# imu_junction.net
KiCad netlist of a schematic drawn in EAGLE
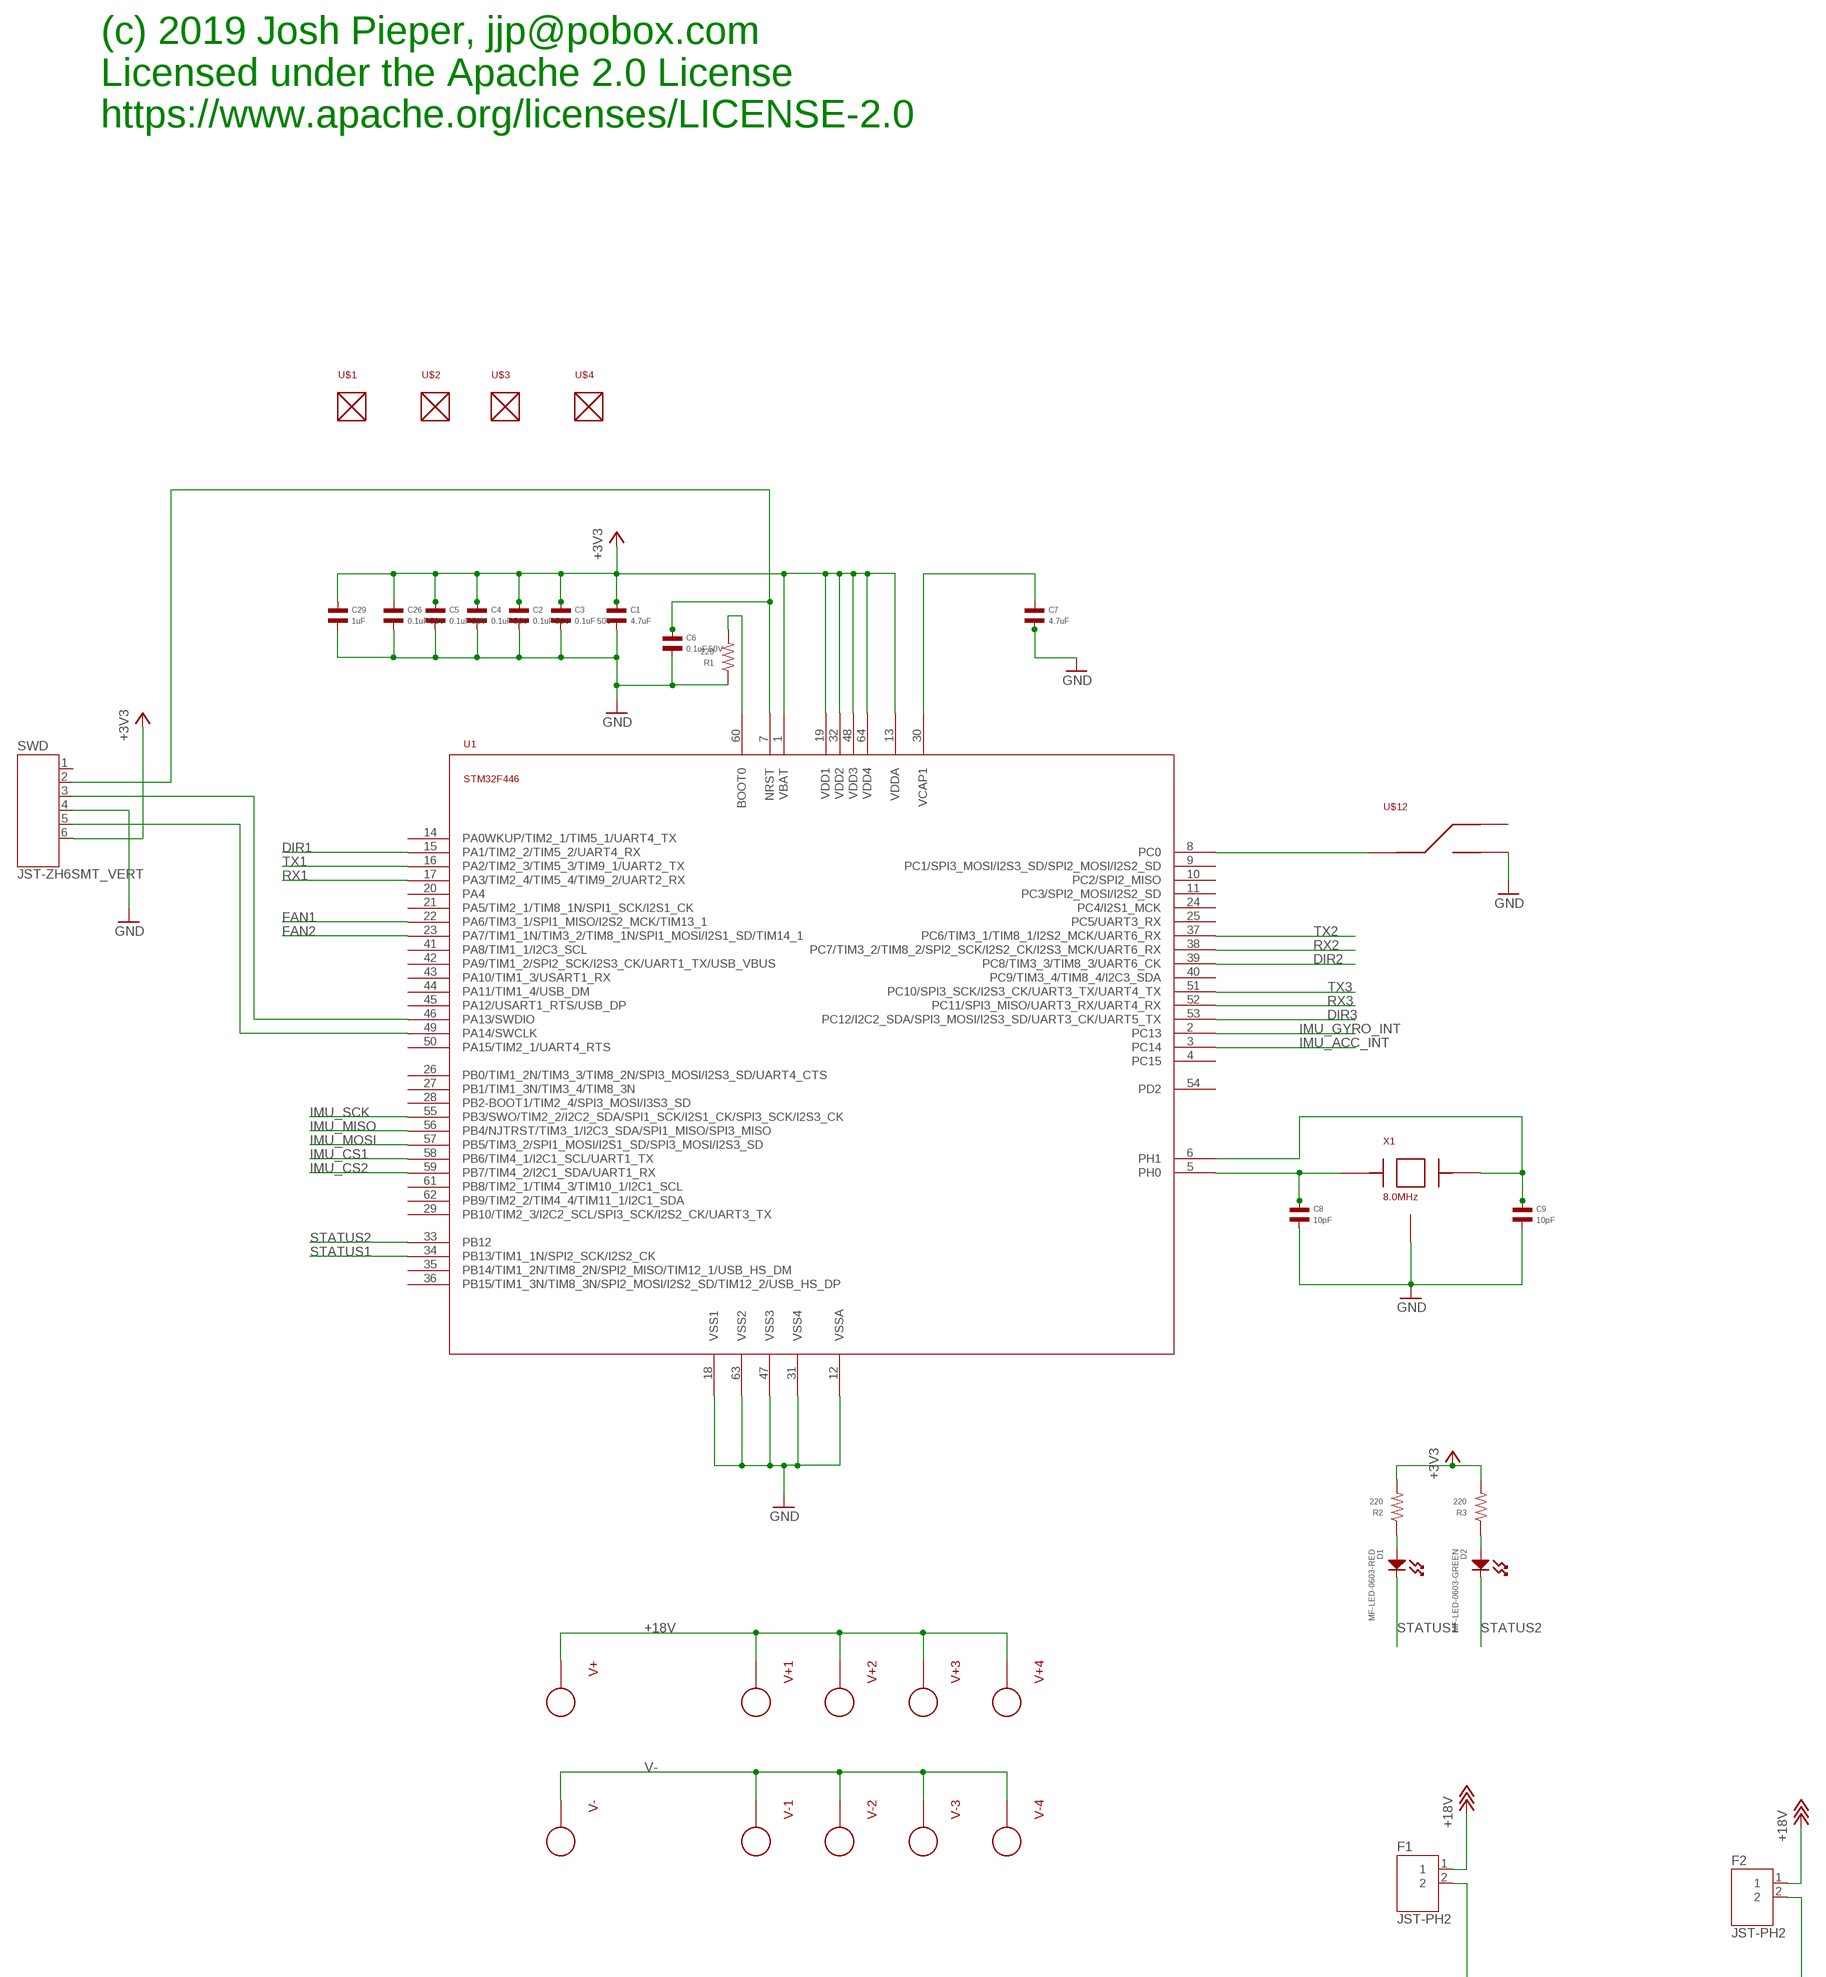
[diagram p0: schematic, sheet 1, part 1 of 2]
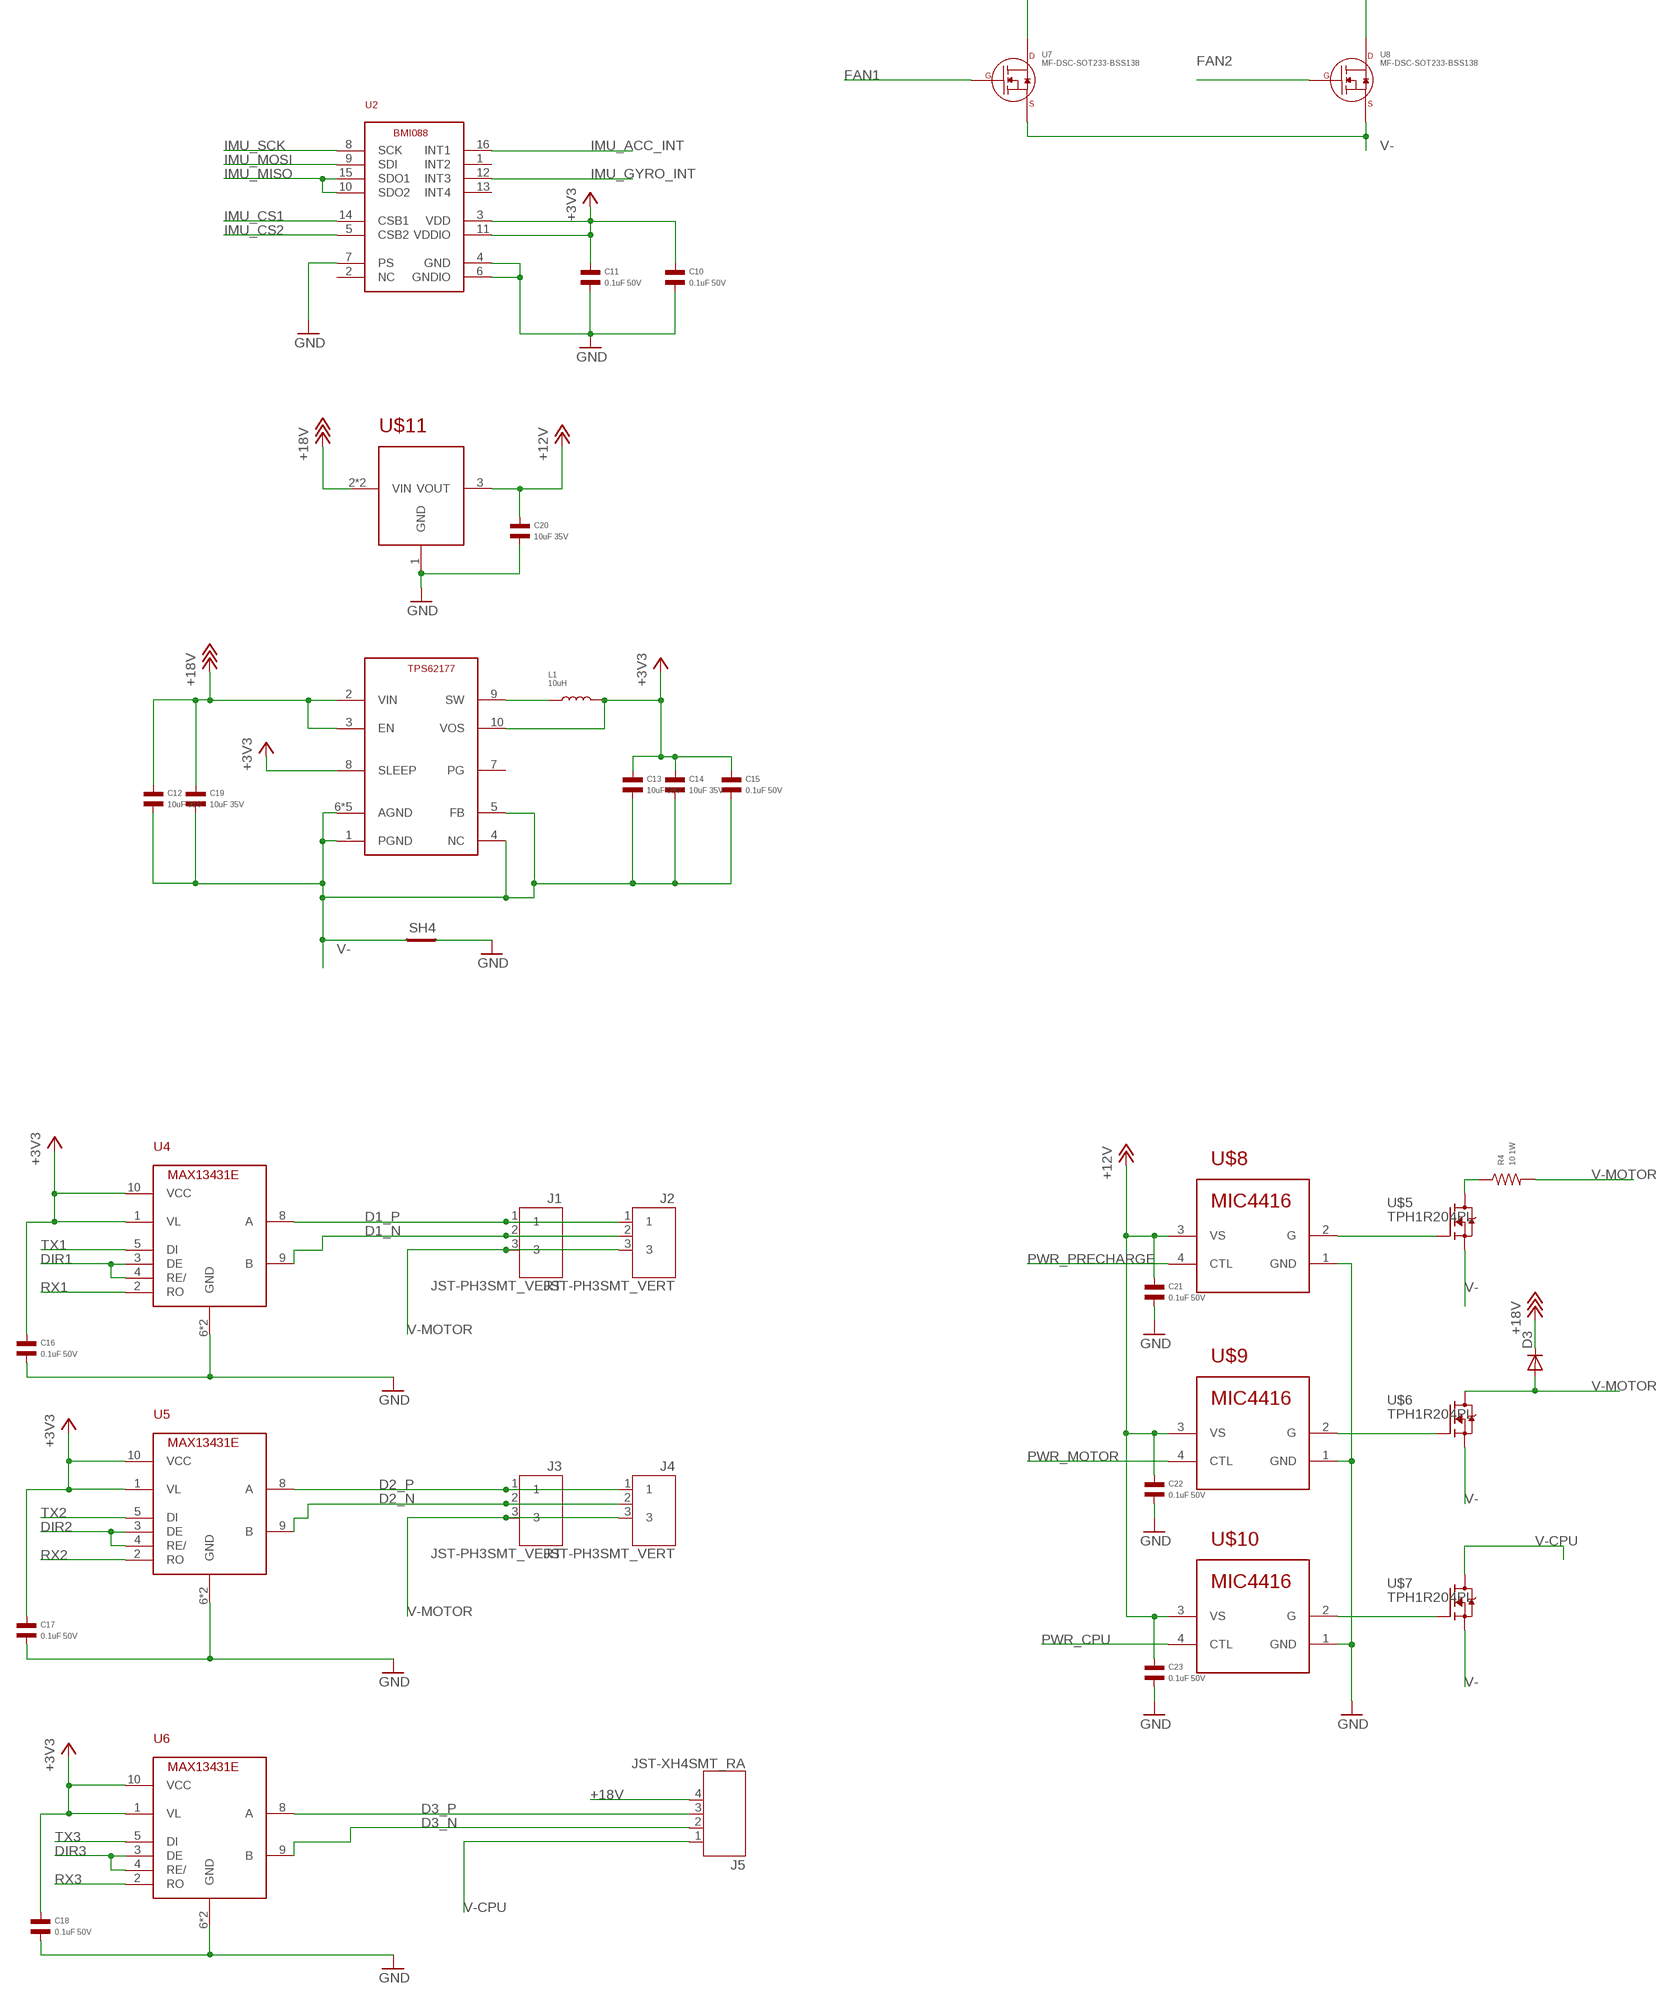
[diagram p1: schematic, sheet 1, part 2 of 2]

(export (version "E")
  (design (tool "Eeschema 10.0.6"))
  (components
    (comp (ref "C1")
      (value "4.7uF")
      (footprint "eagle-import:C0603")
      (fields (field (name "MF") "Samsung Electro-Mechanics") (field (name "MPN") "CL10A475KA8NQNC"))
      (libsource (lib "eagle-import") (part "CAPACITOR_NP_0603"))
    )
    (comp (ref "C2")
      (value "0.1uF 50V")
      (footprint "eagle-import:C0402")
      (fields (field (name "MF") "Walsin") (field (name "MPN") "0402B104K500CT"))
      (libsource (lib "eagle-import") (part "CAPACITOR_NP_0402"))
    )
    (comp (ref "C3")
      (value "0.1uF 50V")
      (footprint "eagle-import:C0402")
      (fields (field (name "MF") "Walsin") (field (name "MPN") "0402B104K500CT"))
      (libsource (lib "eagle-import") (part "CAPACITOR_NP_0402"))
    )
    (comp (ref "C4")
      (value "0.1uF 50V")
      (footprint "eagle-import:C0402")
      (fields (field (name "MF") "Walsin") (field (name "MPN") "0402B104K500CT"))
      (libsource (lib "eagle-import") (part "CAPACITOR_NP_0402"))
    )
    (comp (ref "C5")
      (value "0.1uF 50V")
      (footprint "eagle-import:C0402")
      (fields (field (name "MF") "Walsin") (field (name "MPN") "0402B104K500CT"))
      (libsource (lib "eagle-import") (part "CAPACITOR_NP_0402"))
    )
    (comp (ref "C6")
      (value "0.1uF 50V")
      (footprint "eagle-import:C0402")
      (fields (field (name "MF") "Walsin") (field (name "MPN") "0402B104K500CT"))
      (libsource (lib "eagle-import") (part "CAPACITOR_NP_0402"))
    )
    (comp (ref "C7")
      (value "4.7uF")
      (footprint "eagle-import:C0603")
      (fields (field (name "MF") "Samsung Electro-Mechanics") (field (name "MPN") "CL10A475KA8NQNC"))
      (libsource (lib "eagle-import") (part "CAPACITOR_NP_0603"))
    )
    (comp (ref "C8")
      (value "10pF")
      (footprint "eagle-import:C0603")
      (fields (field (name "HOUSEPART") "1") (field (name "MPN") "MF-CAP-0603-10pF"))
      (libsource (lib "eagle-import") (part "CAPACITOR_NP_0603"))
    )
    (comp (ref "C9")
      (value "10pF")
      (footprint "eagle-import:C0603")
      (fields (field (name "HOUSEPART") "1") (field (name "MPN") "MF-CAP-0603-10pF"))
      (libsource (lib "eagle-import") (part "CAPACITOR_NP_0603"))
    )
    (comp (ref "C10")
      (value "0.1uF 50V")
      (footprint "eagle-import:C0402")
      (fields (field (name "MF") "Walsin") (field (name "MPN") "0402B104K500CT"))
      (libsource (lib "eagle-import") (part "CAPACITOR_NP_0402"))
    )
    (comp (ref "C11")
      (value "0.1uF 50V")
      (footprint "eagle-import:C0402")
      (fields (field (name "MF") "Walsin") (field (name "MPN") "0402B104K500CT"))
      (libsource (lib "eagle-import") (part "CAPACITOR_NP_0402"))
    )
    (comp (ref "C12")
      (value "10uF 35V")
      (footprint "eagle-import:C1206")
      (fields (field (name "MF") "TDK") (field (name "MPN") "CGA5L1X7R1V106K160AC"))
      (libsource (lib "eagle-import") (part "CAPACITOR_NP_1206"))
    )
    (comp (ref "C13")
      (value "10uF 35V")
      (footprint "eagle-import:C1206")
      (fields (field (name "MF") "TDK") (field (name "MPN") "CGA5L1X7R1V106K160AC"))
      (libsource (lib "eagle-import") (part "CAPACITOR_NP_1206"))
    )
    (comp (ref "C14")
      (value "10uF 35V")
      (footprint "eagle-import:C1206")
      (fields (field (name "MF") "TDK") (field (name "MPN") "CGA5L1X7R1V106K160AC"))
      (libsource (lib "eagle-import") (part "CAPACITOR_NP_1206"))
    )
    (comp (ref "C15")
      (value "0.1uF 50V")
      (footprint "eagle-import:C0402")
      (fields (field (name "MF") "Walsin") (field (name "MPN") "0402B104K500CT"))
      (libsource (lib "eagle-import") (part "CAPACITOR_NP_0402"))
    )
    (comp (ref "C16")
      (value "0.1uF 50V")
      (footprint "eagle-import:C0402")
      (fields (field (name "MF") "Walsin") (field (name "MPN") "0402B104K500CT"))
      (libsource (lib "eagle-import") (part "CAPACITOR_NP_0402"))
    )
    (comp (ref "C17")
      (value "0.1uF 50V")
      (footprint "eagle-import:C0402")
      (fields (field (name "MF") "Walsin") (field (name "MPN") "0402B104K500CT"))
      (libsource (lib "eagle-import") (part "CAPACITOR_NP_0402"))
    )
    (comp (ref "C18")
      (value "0.1uF 50V")
      (footprint "eagle-import:C0402")
      (fields (field (name "MF") "Walsin") (field (name "MPN") "0402B104K500CT"))
      (libsource (lib "eagle-import") (part "CAPACITOR_NP_0402"))
    )
    (comp (ref "C19")
      (value "10uF 35V")
      (footprint "eagle-import:C1206")
      (fields (field (name "MF") "TDK") (field (name "MPN") "CGA5L1X7R1V106K160AC"))
      (libsource (lib "eagle-import") (part "CAPACITOR_NP_1206"))
    )
    (comp (ref "C20")
      (value "10uF 35V")
      (footprint "eagle-import:C1206")
      (fields (field (name "MF") "TDK") (field (name "MPN") "CGA5L1X7R1V106K160AC"))
      (libsource (lib "eagle-import") (part "CAPACITOR_NP_1206"))
    )
    (comp (ref "C21")
      (value "0.1uF 50V")
      (footprint "eagle-import:C0402")
      (fields (field (name "MF") "Walsin") (field (name "MPN") "0402B104K500CT"))
      (libsource (lib "eagle-import") (part "CAPACITOR_NP_0402"))
    )
    (comp (ref "C22")
      (value "0.1uF 50V")
      (footprint "eagle-import:C0402")
      (fields (field (name "MF") "Walsin") (field (name "MPN") "0402B104K500CT"))
      (libsource (lib "eagle-import") (part "CAPACITOR_NP_0402"))
    )
    (comp (ref "C23")
      (value "0.1uF 50V")
      (footprint "eagle-import:C0402")
      (fields (field (name "MF") "Walsin") (field (name "MPN") "0402B104K500CT"))
      (libsource (lib "eagle-import") (part "CAPACITOR_NP_0402"))
    )
    (comp (ref "C26")
      (value "0.1uF 50V")
      (footprint "eagle-import:C0402")
      (fields (field (name "MF") "Walsin") (field (name "MPN") "0402B104K500CT"))
      (libsource (lib "eagle-import") (part "CAPACITOR_NP_0402"))
    )
    (comp (ref "C29")
      (value "1uF")
      (footprint "eagle-import:C0402")
      (fields (field (name "HOUSEPART") "YES") (field (name "MPN") "MF-CAP-0402-1uF"))
      (libsource (lib "eagle-import") (part "CAPACITOR_NP_0402"))
    )
    (comp (ref "D1")
      (value "MF-LED-0603-RED")
      (footprint "eagle-import:LED0603")
      (fields (field (name "HOUSEPART") "YES"))
      (libsource (lib "eagle-import") (part "LED_SINGLE-0603-RED"))
    )
    (comp (ref "D2")
      (value "MF-LED-0603-GREEN")
      (footprint "eagle-import:LED0603")
      (fields (field (name "HOUSEPART") "YES"))
      (libsource (lib "eagle-import") (part "LED_SINGLE-0603-GREEN"))
    )
    (comp (ref "D3")
      (value "DIODE-")
      (footprint "eagle-import:DO-214AB")
      (libsource (lib "eagle-import") (part "DIODE-"))
    )
    (comp (ref "F1")
      (value "JST-PH2")
      (footprint "eagle-import:JST_S2B-PH-SM4-TB(LF)(SN)")
      (fields (field (name "MF") "JST") (field (name "MPN") "B2B-PH-SM4-TB(LF)(SN)"))
      (libsource (lib "eagle-import") (part "JST-PH2"))
    )
    (comp (ref "F2")
      (value "JST-PH2")
      (footprint "eagle-import:JST_S2B-PH-SM4-TB(LF)(SN)")
      (fields (field (name "MF") "JST") (field (name "MPN") "B2B-PH-SM4-TB(LF)(SN)"))
      (libsource (lib "eagle-import") (part "JST-PH2"))
    )
    (comp (ref "J1")
      (value "JST-PH3SMT_VERT")
      (footprint "eagle-import:JST_B3B_PH-SM4-TB(LF)(SN)")
      (fields (field (name "MF") "JST") (field (name "MPN") "B3B-PH-SM4-TB(LF)(SN)"))
      (libsource (lib "eagle-import") (part "JST-PH3SMT_VERT"))
    )
    (comp (ref "J2")
      (value "JST-PH3SMT_VERT")
      (footprint "eagle-import:JST_B3B_PH-SM4-TB(LF)(SN)")
      (fields (field (name "MF") "JST") (field (name "MPN") "B3B-PH-SM4-TB(LF)(SN)"))
      (libsource (lib "eagle-import") (part "JST-PH3SMT_VERT"))
    )
    (comp (ref "J3")
      (value "JST-PH3SMT_VERT")
      (footprint "eagle-import:JST_B3B_PH-SM4-TB(LF)(SN)")
      (fields (field (name "MF") "JST") (field (name "MPN") "B3B-PH-SM4-TB(LF)(SN)"))
      (libsource (lib "eagle-import") (part "JST-PH3SMT_VERT"))
    )
    (comp (ref "J4")
      (value "JST-PH3SMT_VERT")
      (footprint "eagle-import:JST_B3B_PH-SM4-TB(LF)(SN)")
      (fields (field (name "MF") "JST") (field (name "MPN") "B3B-PH-SM4-TB(LF)(SN)"))
      (libsource (lib "eagle-import") (part "JST-PH3SMT_VERT"))
    )
    (comp (ref "J5")
      (value "JST-XH4SMT_RA")
      (footprint "eagle-import:JST_XH_SMT_RA_4")
      (fields (field (name "MPN") "S4B-XH-SM4-TB(LF)(SN)"))
      (libsource (lib "eagle-import") (part "JST-XH4SMT_RA"))
    )
    (comp (ref "L1")
      (value "10uH")
      (footprint "eagle-import:L1210")
      (fields
        (field (name "HOUSEPART") "1")
        (field (name "MPN") "MF-IND-1210-10uH")
        (field (name "POPULATE") "1")
      )
      (libsource (lib "eagle-import") (part "INDUCTOR_1210"))
    )
    (comp (ref "R1")
      (value "220")
      (footprint "eagle-import:R0402")
      (fields (field (name "HOUSEPART") "1") (field (name "MPN") "MF-RES-0402-220"))
      (libsource (lib "eagle-import") (part "RESISTOR_0402"))
    )
    (comp (ref "R2")
      (value "220")
      (footprint "eagle-import:R0402")
      (fields (field (name "HOUSEPART") "1") (field (name "MPN") "MF-RES-0402-220"))
      (libsource (lib "eagle-import") (part "RESISTOR_0402"))
    )
    (comp (ref "R3")
      (value "220")
      (footprint "eagle-import:R0402")
      (fields (field (name "HOUSEPART") "1") (field (name "MPN") "MF-RES-0402-220"))
      (libsource (lib "eagle-import") (part "RESISTOR_0402"))
    )
    (comp (ref "R4")
      (value "10 1W")
      (footprint "eagle-import:R1206")
      (fields (field (name "MF") "Susumu") (field (name "MPN") "HRG3216Q-10R0-D-T1"))
      (libsource (lib "eagle-import") (part "RESISTOR_1206"))
    )
    (comp (ref "SH4")
      (value "SHORTBIG")
      (footprint "eagle-import:SHORT_TOP-BIG")
      (libsource (lib "eagle-import") (part "SHORTBIG"))
    )
    (comp (ref "SWD")
      (value "JST-ZH6SMT_VERT")
      (footprint "eagle-import:JST_B6B-ZR-SM4-TF(LF)(SN)")
      (fields (field (name "MF") "JST") (field (name "MPN") "B6B-ZR-SM4-TF(LF)(SN)"))
      (libsource (lib "eagle-import") (part "JST-ZH6SMT_VERT"))
    )
    (comp (ref "U$1")
      (value "MOUNTM2")
      (footprint "eagle-import:M2MOUNT")
      (libsource (lib "eagle-import") (part "MOUNTM2"))
    )
    (comp (ref "U$2")
      (value "MOUNTM2")
      (footprint "eagle-import:M2MOUNT")
      (libsource (lib "eagle-import") (part "MOUNTM2"))
    )
    (comp (ref "U$3")
      (value "MOUNTM2")
      (footprint "eagle-import:M2MOUNT")
      (libsource (lib "eagle-import") (part "MOUNTM2"))
    )
    (comp (ref "U$4")
      (value "MOUNTM2")
      (footprint "eagle-import:M2MOUNT")
      (libsource (lib "eagle-import") (part "MOUNTM2"))
    )
    (comp (ref "U$5")
      (value "TPH1R204PL")
      (footprint "eagle-import:SOP_ADVANCE")
      (fields (field (name "MF") "Toshiba"))
      (libsource (lib "eagle-import") (part "TPH1R204PL"))
    )
    (comp (ref "U$6")
      (value "TPH1R204PL")
      (footprint "eagle-import:SOP_ADVANCE")
      (fields (field (name "MF") "Toshiba"))
      (libsource (lib "eagle-import") (part "TPH1R204PL"))
    )
    (comp (ref "U$7")
      (value "TPH1R204PL")
      (footprint "eagle-import:SOP_ADVANCE")
      (fields (field (name "MF") "Toshiba"))
      (libsource (lib "eagle-import") (part "TPH1R204PL"))
    )
    (comp (ref "U$8")
      (value "MIC4416")
      (footprint "eagle-import:SOT143")
      (fields (field (name "MF") "MICROCHIP") (field (name "MPN") "MIC4416YM4-TR"))
      (libsource (lib "eagle-import") (part "MIC4416"))
    )
    (comp (ref "U$9")
      (value "MIC4416")
      (footprint "eagle-import:SOT143")
      (fields (field (name "MF") "MICROCHIP") (field (name "MPN") "MIC4416YM4-TR"))
      (libsource (lib "eagle-import") (part "MIC4416"))
    )
    (comp (ref "U$10")
      (value "MIC4416")
      (footprint "eagle-import:SOT143")
      (fields (field (name "MF") "MICROCHIP") (field (name "MPN") "MIC4416YM4-TR"))
      (libsource (lib "eagle-import") (part "MIC4416"))
    )
    (comp (ref "U$11")
      (value "ZXTR2012Z")
      (footprint "eagle-import:SOT89")
      (fields (field (name "MF") "DIODES INC"))
      (libsource (lib "eagle-import") (part "ZXTR2012Z"))
    )
    (comp (ref "U$12")
      (value "SLIDE_SWITCHJS_SUB_SWITCH")
      (footprint "eagle-import:JS_SUB_SWITCH")
      (libsource (lib "eagle-import") (part "SLIDE_SWITCHJS_SUB_SWITCH"))
    )
    (comp (ref "U1")
      (value "STM32F4R_64PIN")
      (footprint "eagle-import:LQFP64")
      (fields (field (name "MF") "ST") (field (name "MPN") "STM32F446RET6"))
      (libsource (lib "eagle-import") (part "STM32F4R_64PIN"))
    )
    (comp (ref "U2")
      (value "BMI088LGA16")
      (footprint "eagle-import:LGA16")
      (fields (field (name "MF") "Bosch Sensortec") (field (name "MPN") "BMI088"))
      (libsource (lib "eagle-import") (part "BMI088LGA16"))
    )
    (comp (ref "U3")
      (value "TPS62177WSON10")
      (footprint "eagle-import:WSON10")
      (fields (field (name "MF") "TI") (field (name "MPN") "TPS62177DQCR"))
      (libsource (lib "eagle-import") (part "TPS62177WSON10"))
    )
    (comp (ref "U4")
      (value "MAX13431E")
      (footprint "eagle-import:TDFN10")
      (fields (field (name "MF") "Maxim") (field (name "MPN") "MAX13431EETB+T"))
      (libsource (lib "eagle-import") (part "MAX13431E"))
    )
    (comp (ref "U5")
      (value "MAX13431E")
      (footprint "eagle-import:TDFN10")
      (fields (field (name "MF") "Maxim") (field (name "MPN") "MAX13431EETB+T"))
      (libsource (lib "eagle-import") (part "MAX13431E"))
    )
    (comp (ref "U6")
      (value "MAX13431E")
      (footprint "eagle-import:TDFN10")
      (fields (field (name "MF") "Maxim") (field (name "MPN") "MAX13431EETB+T"))
      (libsource (lib "eagle-import") (part "MAX13431E"))
    )
    (comp (ref "U7")
      (value "MF-DSC-SOT233-BSS138")
      (footprint "eagle-import:SOT-23-3")
      (fields (field (name "HOUSEPART") "YES"))
      (libsource (lib "eagle-import") (part "N-CHANNEL_FET_SOT-23-3_BSS138"))
    )
    (comp (ref "U8")
      (value "MF-DSC-SOT233-BSS138")
      (footprint "eagle-import:SOT-23-3")
      (fields (field (name "HOUSEPART") "YES"))
      (libsource (lib "eagle-import") (part "N-CHANNEL_FET_SOT-23-3_BSS138"))
    )
    (comp (ref "V+")
      (value "PAD12AWG_PAD")
      (footprint "eagle-import:12AWG_PAD")
      (libsource (lib "eagle-import") (part "PAD12AWG_PAD"))
    )
    (comp (ref "V+1")
      (value "PAD12AWG_PAD")
      (footprint "eagle-import:12AWG_PAD")
      (libsource (lib "eagle-import") (part "PAD12AWG_PAD"))
    )
    (comp (ref "V+2")
      (value "PAD12AWG_PAD")
      (footprint "eagle-import:12AWG_PAD")
      (libsource (lib "eagle-import") (part "PAD12AWG_PAD"))
    )
    (comp (ref "V+3")
      (value "PAD12AWG_PAD")
      (footprint "eagle-import:12AWG_PAD")
      (libsource (lib "eagle-import") (part "PAD12AWG_PAD"))
    )
    (comp (ref "V+4")
      (value "PAD12AWG_PAD")
      (footprint "eagle-import:12AWG_PAD")
      (libsource (lib "eagle-import") (part "PAD12AWG_PAD"))
    )
    (comp (ref "V-")
      (value "PAD12AWG_PAD")
      (footprint "eagle-import:12AWG_PAD")
      (libsource (lib "eagle-import") (part "PAD12AWG_PAD"))
    )
    (comp (ref "V-1")
      (value "PAD12AWG_PAD")
      (footprint "eagle-import:12AWG_PAD")
      (libsource (lib "eagle-import") (part "PAD12AWG_PAD"))
    )
    (comp (ref "V-2")
      (value "PAD12AWG_PAD")
      (footprint "eagle-import:12AWG_PAD")
      (libsource (lib "eagle-import") (part "PAD12AWG_PAD"))
    )
    (comp (ref "V-3")
      (value "PAD12AWG_PAD")
      (footprint "eagle-import:12AWG_PAD")
      (libsource (lib "eagle-import") (part "PAD12AWG_PAD"))
    )
    (comp (ref "V-4")
      (value "PAD12AWG_PAD")
      (footprint "eagle-import:12AWG_PAD")
      (libsource (lib "eagle-import") (part "PAD12AWG_PAD"))
    )
    (comp (ref "X1")
      (value "8.0MHz")
      (footprint "eagle-import:ABM3B")
      (fields (field (name "MF") "Abracon") (field (name "MPN") "ABM3B-8.000MHZ-10-1-U-T"))
      (libsource (lib "eagle-import") (part "CRYSTALABM3B"))
    )
  )
  (nets
    (net (code "1") (name "+3V3") (class "Default")
      (node (ref "C1") (pin "P$1") (pinfunction "P$1_P$1") (pintype "passive"))
      (node (ref "C10") (pin "P$1") (pinfunction "P$1_P$1") (pintype "passive"))
      (node (ref "C11") (pin "P$1") (pinfunction "P$1_P$1") (pintype "passive"))
      (node (ref "C13") (pin "P$1") (pinfunction "P$1_P$1") (pintype "passive"))
      (node (ref "C14") (pin "P$1") (pinfunction "P$1_P$1") (pintype "passive"))
      (node (ref "C15") (pin "P$1") (pinfunction "P$1_P$1") (pintype "passive"))
      (node (ref "C16") (pin "P$1") (pinfunction "P$1_P$1") (pintype "passive"))
      (node (ref "C17") (pin "P$1") (pinfunction "P$1_P$1") (pintype "passive"))
      (node (ref "C18") (pin "P$1") (pinfunction "P$1_P$1") (pintype "passive"))
      (node (ref "C2") (pin "P$1") (pinfunction "P$1_P$1") (pintype "passive"))
      (node (ref "C26") (pin "P$1") (pinfunction "P$1_P$1") (pintype "passive"))
      (node (ref "C29") (pin "P$1") (pinfunction "P$1_P$1") (pintype "passive"))
      (node (ref "C3") (pin "P$1") (pinfunction "P$1_P$1") (pintype "passive"))
      (node (ref "C4") (pin "P$1") (pinfunction "P$1_P$1") (pintype "passive"))
      (node (ref "C5") (pin "P$1") (pinfunction "P$1_P$1") (pintype "passive"))
      (node (ref "L1") (pin "P$2") (pinfunction "P$2_P$2") (pintype "passive"))
      (node (ref "R2") (pin "P$2") (pinfunction "P$2_P$2") (pintype "passive"))
      (node (ref "R3") (pin "P$2") (pinfunction "P$2_P$2") (pintype "passive"))
      (node (ref "SWD") (pin "6") (pinfunction "6_6") (pintype "passive"))
      (node (ref "U1") (pin "1") (pinfunction "VBAT_1") (pintype "bidirectional"))
      (node (ref "U1") (pin "13") (pinfunction "VDDA_13") (pintype "bidirectional"))
      (node (ref "U1") (pin "19") (pinfunction "VDD1_19") (pintype "bidirectional"))
      (node (ref "U1") (pin "32") (pinfunction "VDD2_32") (pintype "bidirectional"))
      (node (ref "U1") (pin "48") (pinfunction "VDD3_48") (pintype "bidirectional"))
      (node (ref "U1") (pin "64") (pinfunction "VDD4_64") (pintype "bidirectional"))
      (node (ref "U2") (pin "11") (pinfunction "VDDIO_11") (pintype "bidirectional"))
      (node (ref "U2") (pin "3") (pinfunction "VDD_3") (pintype "bidirectional"))
      (node (ref "U3") (pin "10") (pinfunction "VOS_10") (pintype "bidirectional"))
      (node (ref "U3") (pin "8") (pinfunction "SLEEP_8") (pintype "bidirectional"))
      (node (ref "U4") (pin "1") (pinfunction "VL_1") (pintype "bidirectional"))
      (node (ref "U4") (pin "10") (pinfunction "VCC_10") (pintype "bidirectional"))
      (node (ref "U5") (pin "1") (pinfunction "VL_1") (pintype "bidirectional"))
      (node (ref "U5") (pin "10") (pinfunction "VCC_10") (pintype "bidirectional"))
      (node (ref "U6") (pin "1") (pinfunction "VL_1") (pintype "bidirectional"))
      (node (ref "U6") (pin "10") (pinfunction "VCC_10") (pintype "bidirectional"))
    )
    (net (code "2") (name "+12V") (class "Default")
      (node (ref "C20") (pin "P$1") (pinfunction "P$1_P$1") (pintype "passive"))
      (node (ref "C21") (pin "P$1") (pinfunction "P$1_P$1") (pintype "passive"))
      (node (ref "C22") (pin "P$1") (pinfunction "P$1_P$1") (pintype "passive"))
      (node (ref "C23") (pin "P$1") (pinfunction "P$1_P$1") (pintype "passive"))
      (node (ref "U$10") (pin "3") (pinfunction "VS_3") (pintype "bidirectional"))
      (node (ref "U$11") (pin "3") (pinfunction "VOUT_3") (pintype "bidirectional"))
      (node (ref "U$8") (pin "3") (pinfunction "VS_3") (pintype "bidirectional"))
      (node (ref "U$9") (pin "3") (pinfunction "VS_3") (pintype "bidirectional"))
    )
    (net (code "3") (name "+18V") (class "Default")
      (node (ref "C12") (pin "P$1") (pinfunction "P$1_P$1") (pintype "passive"))
      (node (ref "C19") (pin "P$1") (pinfunction "P$1_P$1") (pintype "passive"))
      (node (ref "D3") (pin "C") (pinfunction "C_C") (pintype "passive"))
      (node (ref "F1") (pin "1") (pinfunction "1_1") (pintype "passive"))
      (node (ref "F2") (pin "1") (pinfunction "1_1") (pintype "passive"))
      (node (ref "J5") (pin "4") (pinfunction "4_4") (pintype "passive"))
      (node (ref "U$11") (pin "2") (pinfunction "VIN_2") (pintype "bidirectional"))
      (node (ref "U$11") (pin "PAD") (pinfunction "VIN_PAD") (pintype "bidirectional"))
      (node (ref "U3") (pin "2") (pinfunction "VIN_2") (pintype "bidirectional"))
      (node (ref "U3") (pin "3") (pinfunction "EN_3") (pintype "bidirectional"))
      (node (ref "V+") (pin "1") (pinfunction "P$1_1") (pintype "bidirectional"))
      (node (ref "V+1") (pin "1") (pinfunction "P$1_1") (pintype "bidirectional"))
      (node (ref "V+2") (pin "1") (pinfunction "P$1_1") (pintype "bidirectional"))
      (node (ref "V+3") (pin "1") (pinfunction "P$1_1") (pintype "bidirectional"))
      (node (ref "V+4") (pin "1") (pinfunction "P$1_1") (pintype "bidirectional"))
    )
    (net (code "4") (name "/D1_N") (class "Default")
      (node (ref "J1") (pin "2") (pinfunction "2_2") (pintype "passive"))
      (node (ref "J2") (pin "2") (pinfunction "2_2") (pintype "passive"))
      (node (ref "U4") (pin "9") (pinfunction "B_9") (pintype "bidirectional"))
    )
    (net (code "5") (name "/D1_P") (class "Default")
      (node (ref "J1") (pin "1") (pinfunction "1_1") (pintype "passive"))
      (node (ref "J2") (pin "1") (pinfunction "1_1") (pintype "passive"))
      (node (ref "U4") (pin "8") (pinfunction "A_8") (pintype "bidirectional"))
    )
    (net (code "6") (name "/D2_N") (class "Default")
      (node (ref "J3") (pin "2") (pinfunction "2_2") (pintype "passive"))
      (node (ref "J4") (pin "2") (pinfunction "2_2") (pintype "passive"))
      (node (ref "U5") (pin "9") (pinfunction "B_9") (pintype "bidirectional"))
    )
    (net (code "7") (name "/D2_P") (class "Default")
      (node (ref "J3") (pin "1") (pinfunction "1_1") (pintype "passive"))
      (node (ref "J4") (pin "1") (pinfunction "1_1") (pintype "passive"))
      (node (ref "U5") (pin "8") (pinfunction "A_8") (pintype "bidirectional"))
    )
    (net (code "8") (name "/D3_N") (class "Default")
      (node (ref "J5") (pin "2") (pinfunction "2_2") (pintype "passive"))
      (node (ref "U6") (pin "9") (pinfunction "B_9") (pintype "bidirectional"))
    )
    (net (code "9") (name "/D3_P") (class "Default")
      (node (ref "J5") (pin "3") (pinfunction "3_3") (pintype "passive"))
      (node (ref "U6") (pin "8") (pinfunction "A_8") (pintype "bidirectional"))
    )
    (net (code "10") (name "/DIR1") (class "Default")
      (node (ref "U1") (pin "15") (pinfunction "PA1/TIM2_2/TIM5_2/UART4_RX_15") (pintype "bidirectional"))
      (node (ref "U4") (pin "3") (pinfunction "DE_3") (pintype "bidirectional"))
      (node (ref "U4") (pin "4") (pinfunction "RE/_4") (pintype "bidirectional"))
    )
    (net (code "11") (name "/DIR2") (class "Default")
      (node (ref "U1") (pin "39") (pinfunction "PC8/TIM3_3/TIM8_3/UART6_CK_39") (pintype "bidirectional"))
      (node (ref "U5") (pin "3") (pinfunction "DE_3") (pintype "bidirectional"))
      (node (ref "U5") (pin "4") (pinfunction "RE/_4") (pintype "bidirectional"))
    )
    (net (code "12") (name "/DIR3") (class "Default")
      (node (ref "U1") (pin "53") (pinfunction "PC12/I2C2_SDA/SPI3_MOSI/I2S3_SD/UART3_CK/UART5_TX_53") (pintype "bidirectional"))
      (node (ref "U6") (pin "3") (pinfunction "DE_3") (pintype "bidirectional"))
      (node (ref "U6") (pin "4") (pinfunction "RE/_4") (pintype "bidirectional"))
    )
    (net (code "13") (name "/FAN1") (class "Default")
      (node (ref "U1") (pin "22") (pinfunction "PA6/TIM3_1/SPI1_MISO/I2S2_MCK/TIM13_1_22") (pintype "bidirectional"))
      (node (ref "U7") (pin "P$1") (pinfunction "GATE_P$1") (pintype "bidirectional"))
    )
    (net (code "14") (name "/FAN2") (class "Default")
      (node (ref "U1") (pin "23") (pinfunction "PA7/TIM1_1N/TIM3_2/TIM8_1N/SPI1_MOSI/I2S1_SD/TIM14_1_23") (pintype "bidirectional"))
      (node (ref "U8") (pin "P$1") (pinfunction "GATE_P$1") (pintype "bidirectional"))
    )
    (net (code "15") (name "/IMU_ACC_INT") (class "Default")
      (node (ref "U1") (pin "3") (pinfunction "PC14_3") (pintype "bidirectional"))
      (node (ref "U2") (pin "16") (pinfunction "INT1_16") (pintype "bidirectional"))
    )
    (net (code "16") (name "/IMU_CS1") (class "Default")
      (node (ref "U1") (pin "58") (pinfunction "PB6/TIM4_1/I2C1_SCL/UART1_TX_58") (pintype "bidirectional"))
      (node (ref "U2") (pin "14") (pinfunction "CSB1_14") (pintype "bidirectional"))
    )
    (net (code "17") (name "/IMU_CS2") (class "Default")
      (node (ref "U1") (pin "59") (pinfunction "PB7/TIM4_2/I2C1_SDA/UART1_RX_59") (pintype "bidirectional"))
      (node (ref "U2") (pin "5") (pinfunction "CSB2_5") (pintype "bidirectional"))
    )
    (net (code "18") (name "/IMU_GYRO_INT") (class "Default")
      (node (ref "U1") (pin "2") (pinfunction "PC13_2") (pintype "bidirectional"))
      (node (ref "U2") (pin "12") (pinfunction "INT3_12") (pintype "bidirectional"))
    )
    (net (code "19") (name "/IMU_MISO") (class "Default")
      (node (ref "U1") (pin "56") (pinfunction "PB4/NJTRST/TIM3_1/I2C3_SDA/SPI1_MISO/SPI3_MISO_56") (pintype "bidirectional"))
      (node (ref "U2") (pin "10") (pinfunction "SDO2_10") (pintype "bidirectional"))
      (node (ref "U2") (pin "15") (pinfunction "SDO1_15") (pintype "bidirectional"))
    )
    (net (code "20") (name "/IMU_MOSI") (class "Default")
      (node (ref "U1") (pin "57") (pinfunction "PB5/TIM3_2/SPI1_MOSI/I2S1_SD/SPI3_MOSI/I2S3_SD_57") (pintype "bidirectional"))
      (node (ref "U2") (pin "9") (pinfunction "SDI_9") (pintype "bidirectional"))
    )
    (net (code "21") (name "/IMU_SCK") (class "Default")
      (node (ref "U1") (pin "55") (pinfunction "PB3/SWO/TIM2_2/I2C2_SDA/SPI1_SCK/I2S1_CK/SPI3_SCK/I2S3_CK_55") (pintype "bidirectional"))
      (node (ref "U2") (pin "8") (pinfunction "SCK_8") (pintype "bidirectional"))
    )
    (net (code "22") (name "/PWR_CPU") (class "Default")
      (node (ref "U$10") (pin "4") (pinfunction "CTL_4") (pintype "bidirectional"))
    )
    (net (code "23") (name "/PWR_MOTOR") (class "Default")
      (node (ref "U$9") (pin "4") (pinfunction "CTL_4") (pintype "bidirectional"))
    )
    (net (code "24") (name "/PWR_PRECHARGE") (class "Default")
      (node (ref "U$8") (pin "4") (pinfunction "CTL_4") (pintype "bidirectional"))
    )
    (net (code "25") (name "/RX1") (class "Default")
      (node (ref "U1") (pin "17") (pinfunction "PA3/TIM2_4/TIM5_4/TIM9_2/UART2_RX_17") (pintype "bidirectional"))
      (node (ref "U4") (pin "2") (pinfunction "RO_2") (pintype "bidirectional"))
    )
    (net (code "26") (name "/RX2") (class "Default")
      (node (ref "U1") (pin "38") (pinfunction "PC7/TIM3_2/TIM8_2/SPI2_SCK/I2S2_CK/I2S3_MCK/UART6_RX_38") (pintype "bidirectional"))
      (node (ref "U5") (pin "2") (pinfunction "RO_2") (pintype "bidirectional"))
    )
    (net (code "27") (name "/RX3") (class "Default")
      (node (ref "U1") (pin "52") (pinfunction "PC11/SPI3_MISO/UART3_RX/UART4_RX_52") (pintype "bidirectional"))
      (node (ref "U6") (pin "2") (pinfunction "RO_2") (pintype "bidirectional"))
    )
    (net (code "28") (name "/STATUS1") (class "Default")
      (node (ref "D1") (pin "CATHODE") (pinfunction "CATHODE_CATHODE") (pintype "power_in"))
      (node (ref "U1") (pin "34") (pinfunction "PB13/TIM1_1N/SPI2_SCK/I2S2_CK_34") (pintype "bidirectional"))
    )
    (net (code "29") (name "/STATUS2") (class "Default")
      (node (ref "D2") (pin "CATHODE") (pinfunction "CATHODE_CATHODE") (pintype "power_in"))
      (node (ref "U1") (pin "33") (pinfunction "PB12_33") (pintype "bidirectional"))
    )
    (net (code "30") (name "/TX1") (class "Default")
      (node (ref "U1") (pin "16") (pinfunction "PA2/TIM2_3/TIM5_3/TIM9_1/UART2_TX_16") (pintype "bidirectional"))
      (node (ref "U4") (pin "5") (pinfunction "DI_5") (pintype "bidirectional"))
    )
    (net (code "31") (name "/TX2") (class "Default")
      (node (ref "U1") (pin "37") (pinfunction "PC6/TIM3_1/TIM8_1/I2S2_MCK/UART6_RX_37") (pintype "bidirectional"))
      (node (ref "U5") (pin "5") (pinfunction "DI_5") (pintype "bidirectional"))
    )
    (net (code "32") (name "/TX3") (class "Default")
      (node (ref "U1") (pin "51") (pinfunction "PC10/SPI3_SCK/I2S3_CK/UART3_TX/UART4_TX_51") (pintype "bidirectional"))
      (node (ref "U6") (pin "5") (pinfunction "DI_5") (pintype "bidirectional"))
    )
    (net (code "33") (name "/V-") (class "Default")
      (node (ref "C12") (pin "P$2") (pinfunction "P$2_P$2") (pintype "passive"))
      (node (ref "C13") (pin "P$2") (pinfunction "P$2_P$2") (pintype "passive"))
      (node (ref "C14") (pin "P$2") (pinfunction "P$2_P$2") (pintype "passive"))
      (node (ref "C15") (pin "P$2") (pinfunction "P$2_P$2") (pintype "passive"))
      (node (ref "C19") (pin "P$2") (pinfunction "P$2_P$2") (pintype "passive"))
      (node (ref "SH4") (pin "1") (pinfunction "P$1_1") (pintype "bidirectional"))
      (node (ref "U$5") (pin "1") (pinfunction "S_1") (pintype "passive"))
      (node (ref "U$5") (pin "2") (pinfunction "S_2") (pintype "passive"))
      (node (ref "U$5") (pin "3") (pinfunction "S_3") (pintype "passive"))
      (node (ref "U$6") (pin "1") (pinfunction "S_1") (pintype "passive"))
      (node (ref "U$6") (pin "2") (pinfunction "S_2") (pintype "passive"))
      (node (ref "U$6") (pin "3") (pinfunction "S_3") (pintype "passive"))
      (node (ref "U$7") (pin "1") (pinfunction "S_1") (pintype "passive"))
      (node (ref "U$7") (pin "2") (pinfunction "S_2") (pintype "passive"))
      (node (ref "U$7") (pin "3") (pinfunction "S_3") (pintype "passive"))
      (node (ref "U3") (pin "1") (pinfunction "PGND_1") (pintype "bidirectional"))
      (node (ref "U3") (pin "4") (pinfunction "NC_4") (pintype "bidirectional"))
      (node (ref "U3") (pin "5") (pinfunction "FB_5") (pintype "bidirectional"))
      (node (ref "U3") (pin "6") (pinfunction "AGND_6") (pintype "bidirectional"))
      (node (ref "U3") (pin "P0") (pinfunction "AGND_P0") (pintype "bidirectional"))
      (node (ref "U3") (pin "P1") (pinfunction "AGND_P1") (pintype "bidirectional"))
      (node (ref "U3") (pin "P2") (pinfunction "AGND_P2") (pintype "bidirectional"))
      (node (ref "U3") (pin "P3") (pinfunction "AGND_P3") (pintype "bidirectional"))
      (node (ref "U7") (pin "P$2") (pinfunction "SOURCE_P$2") (pintype "bidirectional"))
      (node (ref "U8") (pin "P$2") (pinfunction "SOURCE_P$2") (pintype "bidirectional"))
      (node (ref "V-") (pin "1") (pinfunction "P$1_1") (pintype "bidirectional"))
      (node (ref "V-1") (pin "1") (pinfunction "P$1_1") (pintype "bidirectional"))
      (node (ref "V-2") (pin "1") (pinfunction "P$1_1") (pintype "bidirectional"))
      (node (ref "V-3") (pin "1") (pinfunction "P$1_1") (pintype "bidirectional"))
      (node (ref "V-4") (pin "1") (pinfunction "P$1_1") (pintype "bidirectional"))
    )
    (net (code "34") (name "/V-CPU") (class "Default")
      (node (ref "J5") (pin "1") (pinfunction "1_1") (pintype "passive"))
      (node (ref "U$7") (pin "5") (pinfunction "D_5") (pintype "passive"))
      (node (ref "U$7") (pin "6") (pinfunction "D_6") (pintype "passive"))
      (node (ref "U$7") (pin "7") (pinfunction "D_7") (pintype "passive"))
      (node (ref "U$7") (pin "8") (pinfunction "D_8") (pintype "passive"))
      (node (ref "U$7") (pin "PAD") (pinfunction "D_PAD") (pintype "passive"))
    )
    (net (code "35") (name "/V-MOTOR") (class "Default")
      (node (ref "D3") (pin "A") (pinfunction "A_A") (pintype "passive"))
      (node (ref "J1") (pin "3") (pinfunction "3_3") (pintype "passive"))
      (node (ref "J2") (pin "3") (pinfunction "3_3") (pintype "passive"))
      (node (ref "J3") (pin "3") (pinfunction "3_3") (pintype "passive"))
      (node (ref "J4") (pin "3") (pinfunction "3_3") (pintype "passive"))
      (node (ref "R4") (pin "P$2") (pinfunction "P$2_P$2") (pintype "passive"))
      (node (ref "U$6") (pin "5") (pinfunction "D_5") (pintype "passive"))
      (node (ref "U$6") (pin "6") (pinfunction "D_6") (pintype "passive"))
      (node (ref "U$6") (pin "7") (pinfunction "D_7") (pintype "passive"))
      (node (ref "U$6") (pin "8") (pinfunction "D_8") (pintype "passive"))
      (node (ref "U$6") (pin "PAD") (pinfunction "D_PAD") (pintype "passive"))
    )
    (net (code "36") (name "GND") (class "Default")
      (node (ref "C1") (pin "P$2") (pinfunction "P$2_P$2") (pintype "passive"))
      (node (ref "C10") (pin "P$2") (pinfunction "P$2_P$2") (pintype "passive"))
      (node (ref "C11") (pin "P$2") (pinfunction "P$2_P$2") (pintype "passive"))
      (node (ref "C16") (pin "P$2") (pinfunction "P$2_P$2") (pintype "passive"))
      (node (ref "C17") (pin "P$2") (pinfunction "P$2_P$2") (pintype "passive"))
      (node (ref "C18") (pin "P$2") (pinfunction "P$2_P$2") (pintype "passive"))
      (node (ref "C2") (pin "P$2") (pinfunction "P$2_P$2") (pintype "passive"))
      (node (ref "C20") (pin "P$2") (pinfunction "P$2_P$2") (pintype "passive"))
      (node (ref "C21") (pin "P$2") (pinfunction "P$2_P$2") (pintype "passive"))
      (node (ref "C22") (pin "P$2") (pinfunction "P$2_P$2") (pintype "passive"))
      (node (ref "C23") (pin "P$2") (pinfunction "P$2_P$2") (pintype "passive"))
      (node (ref "C26") (pin "P$2") (pinfunction "P$2_P$2") (pintype "passive"))
      (node (ref "C29") (pin "P$2") (pinfunction "P$2_P$2") (pintype "passive"))
      (node (ref "C3") (pin "P$2") (pinfunction "P$2_P$2") (pintype "passive"))
      (node (ref "C4") (pin "P$2") (pinfunction "P$2_P$2") (pintype "passive"))
      (node (ref "C5") (pin "P$2") (pinfunction "P$2_P$2") (pintype "passive"))
      (node (ref "C6") (pin "P$2") (pinfunction "P$2_P$2") (pintype "passive"))
      (node (ref "C7") (pin "P$2") (pinfunction "P$2_P$2") (pintype "passive"))
      (node (ref "C8") (pin "P$2") (pinfunction "P$2_P$2") (pintype "passive"))
      (node (ref "C9") (pin "P$2") (pinfunction "P$2_P$2") (pintype "passive"))
      (node (ref "R1") (pin "P$1") (pinfunction "P$1_P$1") (pintype "passive"))
      (node (ref "SH4") (pin "2") (pinfunction "P$2_2") (pintype "bidirectional"))
      (node (ref "SWD") (pin "4") (pinfunction "4_4") (pintype "passive"))
      (node (ref "U$10") (pin "1") (pinfunction "GND_1") (pintype "bidirectional"))
      (node (ref "U$11") (pin "1") (pinfunction "GND_1") (pintype "bidirectional"))
      (node (ref "U$12") (pin "3") (pinfunction "3_3") (pintype "bidirectional"))
      (node (ref "U$8") (pin "1") (pinfunction "GND_1") (pintype "bidirectional"))
      (node (ref "U$9") (pin "1") (pinfunction "GND_1") (pintype "bidirectional"))
      (node (ref "U1") (pin "12") (pinfunction "VSSA_12") (pintype "bidirectional"))
      (node (ref "U1") (pin "18") (pinfunction "VSS1_18") (pintype "bidirectional"))
      (node (ref "U1") (pin "31") (pinfunction "VSS4_31") (pintype "bidirectional"))
      (node (ref "U1") (pin "47") (pinfunction "VSS3_47") (pintype "bidirectional"))
      (node (ref "U1") (pin "63") (pinfunction "VSS2_63") (pintype "bidirectional"))
      (node (ref "U2") (pin "4") (pinfunction "GND_4") (pintype "bidirectional"))
      (node (ref "U2") (pin "6") (pinfunction "GNDIO_6") (pintype "bidirectional"))
      (node (ref "U2") (pin "7") (pinfunction "PS_7") (pintype "bidirectional"))
      (node (ref "U4") (pin "6") (pinfunction "GND_6") (pintype "bidirectional"))
      (node (ref "U4") (pin "PAD") (pinfunction "GND_PAD") (pintype "bidirectional"))
      (node (ref "U5") (pin "6") (pinfunction "GND_6") (pintype "bidirectional"))
      (node (ref "U5") (pin "PAD") (pinfunction "GND_PAD") (pintype "bidirectional"))
      (node (ref "U6") (pin "6") (pinfunction "GND_6") (pintype "bidirectional"))
      (node (ref "U6") (pin "PAD") (pinfunction "GND_PAD") (pintype "bidirectional"))
      (node (ref "X1") (pin "2") (pinfunction "P$3_2") (pintype "bidirectional"))
      (node (ref "X1") (pin "4") (pinfunction "P$3_4") (pintype "bidirectional"))
    )
    (net (code "37") (name "Net-(D1-PadANODE)") (class "Default")
      (node (ref "D1") (pin "ANODE") (pinfunction "ANODE_ANODE") (pintype "power_in"))
      (node (ref "R2") (pin "P$1") (pinfunction "P$1_P$1") (pintype "passive"))
    )
    (net (code "38") (name "Net-(D2-PadANODE)") (class "Default")
      (node (ref "D2") (pin "ANODE") (pinfunction "ANODE_ANODE") (pintype "power_in"))
      (node (ref "R3") (pin "P$1") (pinfunction "P$1_P$1") (pintype "passive"))
    )
    (net (code "39") (name "Net-(R4-PadP$1)") (class "Default")
      (node (ref "R4") (pin "P$1") (pinfunction "P$1_P$1") (pintype "passive"))
      (node (ref "U$5") (pin "5") (pinfunction "D_5") (pintype "passive"))
      (node (ref "U$5") (pin "6") (pinfunction "D_6") (pintype "passive"))
      (node (ref "U$5") (pin "7") (pinfunction "D_7") (pintype "passive"))
      (node (ref "U$5") (pin "8") (pinfunction "D_8") (pintype "passive"))
      (node (ref "U$5") (pin "PAD") (pinfunction "D_PAD") (pintype "passive"))
    )
    (net (code "40") (name "Net-(U$5-G)") (class "Default")
      (node (ref "U$5") (pin "4") (pinfunction "G_4") (pintype "passive"))
      (node (ref "U$8") (pin "2") (pinfunction "G_2") (pintype "bidirectional"))
    )
    (net (code "41") (name "Net-(U$6-G)") (class "Default")
      (node (ref "U$6") (pin "4") (pinfunction "G_4") (pintype "passive"))
      (node (ref "U$9") (pin "2") (pinfunction "G_2") (pintype "bidirectional"))
    )
    (net (code "42") (name "Net-(U$10-G)") (class "Default")
      (node (ref "U$10") (pin "2") (pinfunction "G_2") (pintype "bidirectional"))
      (node (ref "U$7") (pin "4") (pinfunction "G_4") (pintype "passive"))
    )
    (net (code "43") (name "Net-(U1-BOOT0)") (class "Default")
      (node (ref "R1") (pin "P$2") (pinfunction "P$2_P$2") (pintype "passive"))
      (node (ref "U1") (pin "60") (pinfunction "BOOT0_60") (pintype "bidirectional"))
    )
    (net (code "44") (name "Net-(U1-NRST)") (class "Default")
      (node (ref "C6") (pin "P$1") (pinfunction "P$1_P$1") (pintype "passive"))
      (node (ref "SWD") (pin "2") (pinfunction "2_2") (pintype "passive"))
      (node (ref "U1") (pin "7") (pinfunction "NRST_7") (pintype "bidirectional"))
    )
    (net (code "45") (name "Net-(U1-PA13{slash}SWDIO)") (class "Default")
      (node (ref "SWD") (pin "3") (pinfunction "3_3") (pintype "passive"))
      (node (ref "U1") (pin "46") (pinfunction "PA13/SWDIO_46") (pintype "bidirectional"))
    )
    (net (code "46") (name "Net-(U1-PA14{slash}SWCLK)") (class "Default")
      (node (ref "SWD") (pin "5") (pinfunction "5_5") (pintype "passive"))
      (node (ref "U1") (pin "49") (pinfunction "PA14/SWCLK_49") (pintype "bidirectional"))
    )
    (net (code "47") (name "Net-(U1-PC0)") (class "Default")
      (node (ref "U$12") (pin "2") (pinfunction "2_2") (pintype "bidirectional"))
      (node (ref "U1") (pin "8") (pinfunction "PC0_8") (pintype "bidirectional"))
    )
    (net (code "48") (name "Net-(U1-PH0)") (class "Default")
      (node (ref "C8") (pin "P$1") (pinfunction "P$1_P$1") (pintype "passive"))
      (node (ref "U1") (pin "5") (pinfunction "PH0_5") (pintype "bidirectional"))
      (node (ref "X1") (pin "1") (pinfunction "P$1_1") (pintype "bidirectional"))
    )
    (net (code "49") (name "Net-(U1-PH1)") (class "Default")
      (node (ref "C9") (pin "P$1") (pinfunction "P$1_P$1") (pintype "passive"))
      (node (ref "U1") (pin "6") (pinfunction "PH1_6") (pintype "bidirectional"))
      (node (ref "X1") (pin "3") (pinfunction "P$2_3") (pintype "bidirectional"))
    )
    (net (code "50") (name "Net-(U1-VCAP1)") (class "Default")
      (node (ref "C7") (pin "P$1") (pinfunction "P$1_P$1") (pintype "passive"))
      (node (ref "U1") (pin "30") (pinfunction "VCAP1_30") (pintype "bidirectional"))
    )
    (net (code "51") (name "Net-(U3-SW)") (class "Default")
      (node (ref "L1") (pin "P$1") (pinfunction "P$1_P$1") (pintype "passive"))
      (node (ref "U3") (pin "9") (pinfunction "SW_9") (pintype "bidirectional"))
    )
    (net (code "52") (name "Net-(U7-DRAIN)") (class "Default")
      (node (ref "F1") (pin "2") (pinfunction "2_2") (pintype "passive"))
      (node (ref "U7") (pin "P$3") (pinfunction "DRAIN_P$3") (pintype "bidirectional"))
    )
    (net (code "53") (name "Net-(U8-DRAIN)") (class "Default")
      (node (ref "F2") (pin "2") (pinfunction "2_2") (pintype "passive"))
      (node (ref "U8") (pin "P$3") (pinfunction "DRAIN_P$3") (pintype "bidirectional"))
    )
    (net (code "54") (name "unconnected-(SWD-Pad1)") (class "Default")
      (node (ref "SWD") (pin "1") (pinfunction "1_1") (pintype "passive"))
    )
    (net (code "55") (name "unconnected-(U$12-Pad1)") (class "Default")
      (node (ref "U$12") (pin "1") (pinfunction "1_1") (pintype "bidirectional"))
    )
    (net (code "56") (name "unconnected-(U1-PA0WKUP{slash}TIM2_1{slash}TIM5_1{slash}UART4_TX-Pad14)") (class "Default")
      (node (ref "U1") (pin "14") (pinfunction "PA0WKUP/TIM2_1/TIM5_1/UART4_TX_14") (pintype "bidirectional"))
    )
    (net (code "57") (name "unconnected-(U1-PA4-Pad20)") (class "Default")
      (node (ref "U1") (pin "20") (pinfunction "PA4_20") (pintype "bidirectional"))
    )
    (net (code "58") (name "unconnected-(U1-PA5{slash}TIM2_1{slash}TIM8_1N{slash}SPI1_SCK{slash}I2S1_CK-Pad21)") (class "Default")
      (node (ref "U1") (pin "21") (pinfunction "PA5/TIM2_1/TIM8_1N/SPI1_SCK/I2S1_CK_21") (pintype "bidirectional"))
    )
    (net (code "59") (name "unconnected-(U1-PA8{slash}TIM1_1{slash}I2C3_SCL-Pad41)") (class "Default")
      (node (ref "U1") (pin "41") (pinfunction "PA8/TIM1_1/I2C3_SCL_41") (pintype "bidirectional"))
    )
    (net (code "60") (name "unconnected-(U1-PA9{slash}TIM1_2{slash}SPI2_SCK{slash}I2S3_CK{slash}UART1_TX{slash}USB_VBUS-Pad42)") (class "Default")
      (node (ref "U1") (pin "42") (pinfunction "PA9/TIM1_2/SPI2_SCK/I2S3_CK/UART1_TX/USB_VBUS_42") (pintype "bidirectional"))
    )
    (net (code "61") (name "unconnected-(U1-PA10{slash}TIM1_3{slash}USART1_RX-Pad43)") (class "Default")
      (node (ref "U1") (pin "43") (pinfunction "PA10/TIM1_3/USART1_RX_43") (pintype "bidirectional"))
    )
    (net (code "62") (name "unconnected-(U1-PA11{slash}TIM1_4{slash}USB_DM-Pad44)") (class "Default")
      (node (ref "U1") (pin "44") (pinfunction "PA11/TIM1_4/USB_DM_44") (pintype "bidirectional"))
    )
    (net (code "63") (name "unconnected-(U1-PA12{slash}USART1_RTS{slash}USB_DP-Pad45)") (class "Default")
      (node (ref "U1") (pin "45") (pinfunction "PA12/USART1_RTS/USB_DP_45") (pintype "bidirectional"))
    )
    (net (code "64") (name "unconnected-(U1-PA15{slash}TIM2_1{slash}UART4_RTS-Pad50)") (class "Default")
      (node (ref "U1") (pin "50") (pinfunction "PA15/TIM2_1/UART4_RTS_50") (pintype "bidirectional"))
    )
    (net (code "65") (name "unconnected-(U1-PB0{slash}TIM1_2N{slash}TIM3_3{slash}TIM8_2N{slash}SPI3_MOSI{slash}I2S3_SD{slash}UART4_CTS-Pad26)") (class "Default")
      (node (ref "U1") (pin "26") (pinfunction "PB0/TIM1_2N/TIM3_3/TIM8_2N/SPI3_MOSI/I2S3_SD/UART4_CTS_26") (pintype "bidirectional"))
    )
    (net (code "66") (name "unconnected-(U1-PB1{slash}TIM1_3N{slash}TIM3_4{slash}TIM8_3N-Pad27)") (class "Default")
      (node (ref "U1") (pin "27") (pinfunction "PB1/TIM1_3N/TIM3_4/TIM8_3N_27") (pintype "bidirectional"))
    )
    (net (code "67") (name "unconnected-(U1-PB2-BOOT1{slash}TIM2_4{slash}SPI3_MOSI{slash}I3S3_SD-Pad28)") (class "Default")
      (node (ref "U1") (pin "28") (pinfunction "PB2-BOOT1/TIM2_4/SPI3_MOSI/I3S3_SD_28") (pintype "bidirectional"))
    )
    (net (code "68") (name "unconnected-(U1-PB8{slash}TIM2_1{slash}TIM4_3{slash}TIM10_1{slash}I2C1_SCL-Pad61)") (class "Default")
      (node (ref "U1") (pin "61") (pinfunction "PB8/TIM2_1/TIM4_3/TIM10_1/I2C1_SCL_61") (pintype "bidirectional"))
    )
    (net (code "69") (name "unconnected-(U1-PB9{slash}TIM2_2{slash}TIM4_4{slash}TIM11_1{slash}I2C1_SDA-Pad62)") (class "Default")
      (node (ref "U1") (pin "62") (pinfunction "PB9/TIM2_2/TIM4_4/TIM11_1/I2C1_SDA_62") (pintype "bidirectional"))
    )
    (net (code "70") (name "unconnected-(U1-PB10{slash}TIM2_3{slash}I2C2_SCL{slash}SPI3_SCK{slash}I2S2_CK{slash}UART3_TX-Pad29)") (class "Default")
      (node (ref "U1") (pin "29") (pinfunction "PB10/TIM2_3/I2C2_SCL/SPI3_SCK/I2S2_CK/UART3_TX_29") (pintype "bidirectional"))
    )
    (net (code "71") (name "unconnected-(U1-PB14{slash}TIM1_2N{slash}TIM8_2N{slash}SPI2_MISO{slash}TIM12_1{slash}USB_HS_DM-Pad35)") (class "Default")
      (node (ref "U1") (pin "35") (pinfunction "PB14/TIM1_2N/TIM8_2N/SPI2_MISO/TIM12_1/USB_HS_DM_35") (pintype "bidirectional"))
    )
    (net (code "72") (name "unconnected-(U1-PB15{slash}TIM1_3N{slash}TIM8_3N{slash}SPI2_MOSI{slash}I2S2_SD{slash}TIM12_2{slash}USB_HS_DP-Pad36)") (class "Default")
      (node (ref "U1") (pin "36") (pinfunction "PB15/TIM1_3N/TIM8_3N/SPI2_MOSI/I2S2_SD/TIM12_2/USB_HS_DP_36") (pintype "bidirectional"))
    )
    (net (code "73") (name "unconnected-(U1-PC1{slash}SPI3_MOSI{slash}I2S3_SD{slash}SPI2_MOSI{slash}I2S2_SD-Pad9)") (class "Default")
      (node (ref "U1") (pin "9") (pinfunction "PC1/SPI3_MOSI/I2S3_SD/SPI2_MOSI/I2S2_SD_9") (pintype "bidirectional"))
    )
    (net (code "74") (name "unconnected-(U1-PC2{slash}SPI2_MISO-Pad10)") (class "Default")
      (node (ref "U1") (pin "10") (pinfunction "PC2/SPI2_MISO_10") (pintype "bidirectional"))
    )
    (net (code "75") (name "unconnected-(U1-PC3{slash}SPI2_MOSI{slash}I2S2_SD-Pad11)") (class "Default")
      (node (ref "U1") (pin "11") (pinfunction "PC3/SPI2_MOSI/I2S2_SD_11") (pintype "bidirectional"))
    )
    (net (code "76") (name "unconnected-(U1-PC4{slash}I2S1_MCK-Pad24)") (class "Default")
      (node (ref "U1") (pin "24") (pinfunction "PC4/I2S1_MCK_24") (pintype "bidirectional"))
    )
    (net (code "77") (name "unconnected-(U1-PC5{slash}UART3_RX-Pad25)") (class "Default")
      (node (ref "U1") (pin "25") (pinfunction "PC5/UART3_RX_25") (pintype "bidirectional"))
    )
    (net (code "78") (name "unconnected-(U1-PC9{slash}TIM3_4{slash}TIM8_4{slash}I2C3_SDA-Pad40)") (class "Default")
      (node (ref "U1") (pin "40") (pinfunction "PC9/TIM3_4/TIM8_4/I2C3_SDA_40") (pintype "bidirectional"))
    )
    (net (code "79") (name "unconnected-(U1-PC15-Pad4)") (class "Default")
      (node (ref "U1") (pin "4") (pinfunction "PC15_4") (pintype "bidirectional"))
    )
    (net (code "80") (name "unconnected-(U1-PD2-Pad54)") (class "Default")
      (node (ref "U1") (pin "54") (pinfunction "PD2_54") (pintype "bidirectional"))
    )
    (net (code "81") (name "unconnected-(U2-INT2-Pad1)") (class "Default")
      (node (ref "U2") (pin "1") (pinfunction "INT2_1") (pintype "bidirectional"))
    )
    (net (code "82") (name "unconnected-(U2-INT4-Pad13)") (class "Default")
      (node (ref "U2") (pin "13") (pinfunction "INT4_13") (pintype "bidirectional"))
    )
    (net (code "83") (name "unconnected-(U2-NC-Pad2)") (class "Default")
      (node (ref "U2") (pin "2") (pinfunction "NC_2") (pintype "bidirectional"))
    )
    (net (code "84") (name "unconnected-(U3-PG-Pad7)") (class "Default")
      (node (ref "U3") (pin "7") (pinfunction "PG_7") (pintype "bidirectional"))
    )
  )
)
